# 4-APPS.net
KiCad netlist of a schematic drawn in Altium Designer
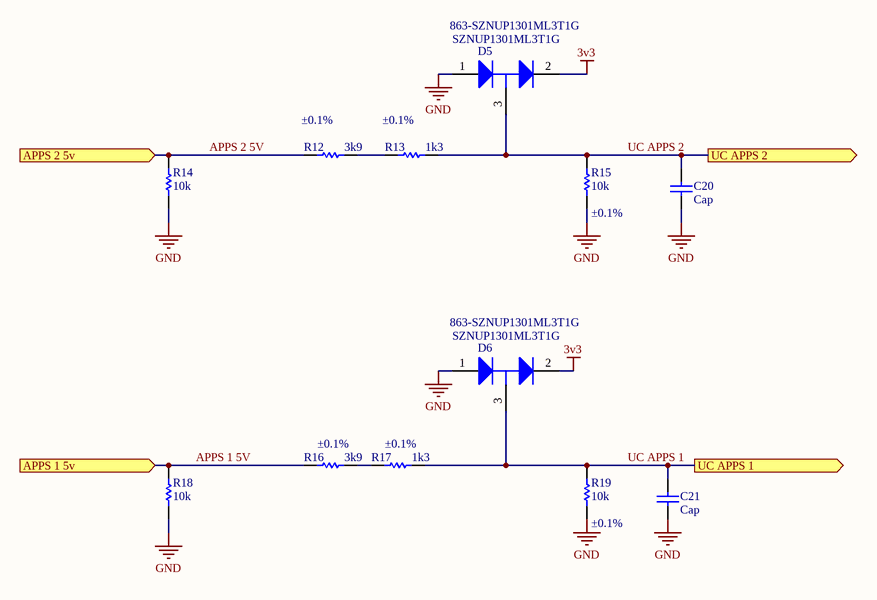
[diagram p0: 4-APPS.SchDoc]

(export (version "E")
  (design (tool "Eeschema 10.0.6"))
  (components
    (comp (ref "C20")
      (value "Cap")
      (footprint "1608[0603]")
      (description "CAP 4.7uF 25V ±10% 1210 (3225 Metric) Thickness 2.2mm SMD")
      (fields (field (name "TOLERANCE") "Â±10%"))
      (libsource (lib "Altium Content Vault") (part "CAP"))
    )
    (comp (ref "C21")
      (value "Cap")
      (footprint "1608[0603]")
      (description "CAP 4.7uF 25V ±10% 1210 (3225 Metric) Thickness 2.2mm SMD")
      (fields (field (name "TOLERANCE") "Â±10%"))
      (libsource (lib "Altium Content Vault") (part "CAP"))
    )
    (comp (ref "D5")
      (value "SZNUP1301ML3T1G")
      (footprint "ONSC-SOT-23-3-318-08_V")
      (fields
        (field (name "MANUFACTURER") "On Semiconductor")
        (field (name "SUPPLIER PART NUMBER 1") "863-SZNUP1301ML3T1G")
      )
      (libsource (lib "Altium Content Vault") (part "ONSC-NUP1301-SOT-23-3-318-08"))
    )
    (comp (ref "D6")
      (value "SZNUP1301ML3T1G")
      (footprint "ONSC-SOT-23-3-318-08_V")
      (fields
        (field (name "MANUFACTURER") "On Semiconductor")
        (field (name "SUPPLIER PART NUMBER 1") "863-SZNUP1301ML3T1G")
      )
      (libsource (lib "Altium Content Vault") (part "ONSC-NUP1301-SOT-23-3-318-08"))
    )
    (comp (ref "R12")
      (value "3k9")
      (footprint "1608[0603]")
      (description "Resistor")
      (fields
        (field (name "MANUFACTURER") "Yageo")
        (field (name "MANUFACTURER PART NUMBER") "RT0603BRD073K9L")
        (field (name "TOLERANCE") "±0.1%")
      )
      (libsource (lib "Miscellaneous Devices") (part "Res1"))
    )
    (comp (ref "R13")
      (value "1k3")
      (footprint "1608[0603]")
      (description "Resistor")
      (fields
        (field (name "MANUFACTURER") "Yageo")
        (field (name "MANUFACTURER PART NUMBER") "RT0603BRD071K3L")
        (field (name "TOLERANCE") "±0.1%")
      )
      (libsource (lib "Miscellaneous Devices") (part "Res1"))
    )
    (comp (ref "R14")
      (value "10k")
      (footprint "1608[0603]")
      (description "Resistor")
      (fields
        (field (name "MANUFACTURER") "Yageo")
        (field (name "MANUFACTURER PART NUMBER") "RC0603JR-0710KL")
      )
      (libsource (lib "Miscellaneous Devices") (part "Res1"))
    )
    (comp (ref "R15")
      (value "10k")
      (footprint "1608[0603]")
      (description "Resistor")
      (fields
        (field (name "MANUFACTURER") "Yageo")
        (field (name "MANUFACTURER PART NUMBER") "RT0603BRD0710KL")
        (field (name "TOLERANCE") "±0.1%")
      )
      (libsource (lib "Miscellaneous Devices") (part "Res1"))
    )
    (comp (ref "R16")
      (value "3k9")
      (footprint "1608[0603]")
      (description "Resistor")
      (fields
        (field (name "MANUFACTURER") "Yageo")
        (field (name "MANUFACTURER PART NUMBER") "RT0603BRD073K9L")
        (field (name "TOLERANCE") "±0.1%")
      )
      (libsource (lib "Miscellaneous Devices") (part "Res1"))
    )
    (comp (ref "R17")
      (value "1k3")
      (footprint "1608[0603]")
      (description "Resistor")
      (fields
        (field (name "MANUFACTURER") "Yageo")
        (field (name "MANUFACTURER PART NUMBER") "RT0603BRD071K3L")
        (field (name "TOLERANCE") "±0.1%")
      )
      (libsource (lib "Miscellaneous Devices") (part "Res1"))
    )
    (comp (ref "R18")
      (value "10k")
      (footprint "1608[0603]")
      (description "Resistor")
      (fields
        (field (name "MANUFACTURER") "Yageo")
        (field (name "MANUFACTURER PART NUMBER") "RC0603JR-0710KL")
      )
      (libsource (lib "Miscellaneous Devices") (part "Res1"))
    )
    (comp (ref "R19")
      (value "10k")
      (footprint "1608[0603]")
      (description "Resistor")
      (fields
        (field (name "MANUFACTURER") "Yageo")
        (field (name "MANUFACTURER PART NUMBER") "RT0603BRD0710KL")
        (field (name "TOLERANCE") "±0.1%")
      )
      (libsource (lib "Miscellaneous Devices") (part "Res1"))
    )
  )
  (nets
    (net (code "1") (name "/APPS 1 5V") (class "Default")
      (node (ref "R16") (pin "1") (pinfunction "1_1") (pintype "passive"))
      (node (ref "R18") (pin "2") (pinfunction "2_2") (pintype "passive"))
    )
    (net (code "2") (name "/APPS 2 5V") (class "Default")
      (node (ref "R12") (pin "1") (pinfunction "1_1") (pintype "passive"))
      (node (ref "R14") (pin "2") (pinfunction "2_2") (pintype "passive"))
    )
    (net (code "3") (name "/UC APPS 1") (class "Default")
      (node (ref "C21") (pin "2") (pinfunction "2_2") (pintype "passive"))
      (node (ref "D6") (pin "3") (pinfunction "K/A_3") (pintype "passive"))
      (node (ref "R17") (pin "2") (pinfunction "2_2") (pintype "passive"))
      (node (ref "R19") (pin "2") (pinfunction "2_2") (pintype "passive"))
    )
    (net (code "4") (name "/UC APPS 2") (class "Default")
      (node (ref "C20") (pin "2") (pinfunction "2_2") (pintype "passive"))
      (node (ref "D5") (pin "3") (pinfunction "K/A_3") (pintype "passive"))
      (node (ref "R13") (pin "2") (pinfunction "2_2") (pintype "passive"))
      (node (ref "R15") (pin "2") (pinfunction "2_2") (pintype "passive"))
    )
    (net (code "5") (name "3v3") (class "Default")
      (node (ref "D5") (pin "2") (pinfunction "K_2") (pintype "passive"))
      (node (ref "D6") (pin "2") (pinfunction "K_2") (pintype "passive"))
    )
    (net (code "6") (name "GND") (class "Default")
      (node (ref "C20") (pin "1") (pinfunction "1_1") (pintype "passive"))
      (node (ref "C21") (pin "1") (pinfunction "1_1") (pintype "passive"))
      (node (ref "D5") (pin "1") (pinfunction "A_1") (pintype "passive"))
      (node (ref "D6") (pin "1") (pinfunction "A_1") (pintype "passive"))
      (node (ref "R14") (pin "1") (pinfunction "1_1") (pintype "passive"))
      (node (ref "R15") (pin "1") (pinfunction "1_1") (pintype "passive"))
      (node (ref "R18") (pin "1") (pinfunction "1_1") (pintype "passive"))
      (node (ref "R19") (pin "1") (pinfunction "1_1") (pintype "passive"))
    )
    (net (code "7") (name "Net-(R12-Pad2)") (class "Default")
      (node (ref "R12") (pin "2") (pinfunction "2_2") (pintype "passive"))
      (node (ref "R13") (pin "1") (pinfunction "1_1") (pintype "passive"))
    )
    (net (code "8") (name "Net-(R16-Pad2)") (class "Default")
      (node (ref "R16") (pin "2") (pinfunction "2_2") (pintype "passive"))
      (node (ref "R17") (pin "1") (pinfunction "1_1") (pintype "passive"))
    )
  )
)
